# power_supply.net
KiCad netlist of a schematic drawn in Altium Designer
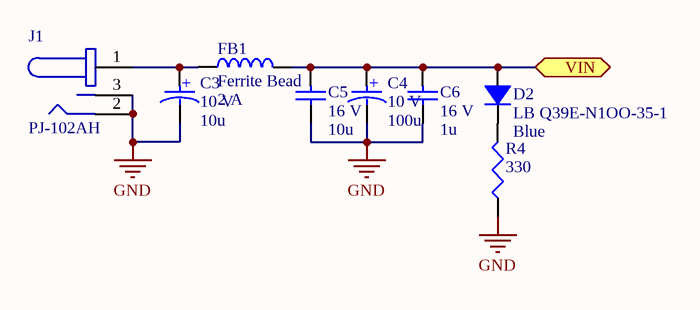
[diagram p0: power_supply.SchDoc]

(export (version "E")
  (design (tool "Eeschema 10.0.6"))
  (components
    (comp (ref "C3")
      (value "10u")
      (footprint "0603 - Polar Marking")
      (description "Tantalum capacitor, 10 uF, 10 V, 0603 package")
      (fields
        (field (name "TOLERANCE") "10%")
        (field (name "VOLTAGE RATED") "10 V")
        (field (name "Comment") "Tantalum capacitor")
      )
      (libsource (lib "rlc") (part "C_10u_10V_0603_tantalum"))
    )
    (comp (ref "C4")
      (value "100u")
      (footprint "2917")
      (description "Tantalum capacitor, 100u, 2917 package")
      (fields
        (field (name "TOLERANCE") "10%")
        (field (name "VOLTAGE RATED") "10 V")
        (field (name "Comment") "Ceramic capacitor")
      )
      (libsource (lib "rlc") (part "C_100u_10V_2917_tantalum"))
    )
    (comp (ref "C5")
      (value "10u")
      (footprint "0603")
      (description "Ceramic capacitor, 10 uF, 16 V, 0603 package")
      (fields
        (field (name "TOLERANCE") "20%")
        (field (name "VOLTAGE RATED") "16 V")
        (field (name "Comment") "Ceramic capacitor")
      )
      (libsource (lib "rlc") (part "C_10u_16V_0603_ceramic"))
    )
    (comp (ref "C6")
      (value "1u")
      (footprint "0603")
      (description "Ceramic capacitor, 1 uF, 16 V, 0603 package")
      (fields
        (field (name "TOLERANCE") "10%")
        (field (name "VOLTAGE RATED") "16 V")
        (field (name "Comment") "Ceramic capacitor")
      )
      (libsource (lib "rlc") (part "C_1u_16V_0603_ceramic"))
    )
    (comp (ref "D2")
      (value "LB Q39E-N1OO-35-1")
      (footprint "0603 - LED")
      (description "LED, Blue, 0603")
      (fields (field (name "COLOR") "Blue"))
      (libsource (lib "rlc") (part "D_LED_Blue_0603"))
    )
    (comp (ref "FB1")
      (value "Ferrite Bead")
      (footprint "0603")
      (description "Ferrite Bead, 2 A, 0603 package")
      (fields (field (name "CURRENT RATING") "2 A"))
      (libsource (lib "rlc") (part "FB_2A_0603"))
    )
    (comp (ref "J1")
      (value "PJ-102AH")
      (footprint "PJ-102AH")
      (description "CONN PWR JACK 2.1X5.5MM HIGH CUR")
      (libsource (lib "connectors") (part "PJ-102AH"))
    )
    (comp (ref "R4")
      (value "330")
      (footprint "0603")
      (description "Chip resistor, 330, 0603 package")
      (fields (field (name "TOLERANCE") "1%") (field (name "POWER") "1/10 W"))
      (libsource (lib "rlc") (part "R_330_0603"))
    )
  )
  (nets
    (net (code "1") (name "/VIN") (class "Default")
      (node (ref "C4") (pin "1") (pintype "passive"))
      (node (ref "C5") (pin "1") (pintype "passive"))
      (node (ref "C6") (pin "1") (pintype "passive"))
      (node (ref "D2") (pin "1") (pintype "passive"))
      (node (ref "FB1") (pin "1") (pintype "passive"))
    )
    (net (code "2") (name "GND") (class "Default")
      (node (ref "C3") (pin "2") (pintype "passive"))
      (node (ref "C4") (pin "2") (pintype "passive"))
      (node (ref "C5") (pin "2") (pintype "passive"))
      (node (ref "C6") (pin "2") (pintype "passive"))
      (node (ref "J1") (pin "2") (pintype "passive"))
      (node (ref "J1") (pin "3") (pintype "passive"))
      (node (ref "R4") (pin "2") (pintype "passive"))
    )
    (net (code "3") (name "Net-(C3-Pad1)") (class "Default")
      (node (ref "C3") (pin "1") (pintype "passive"))
      (node (ref "FB1") (pin "2") (pintype "passive"))
      (node (ref "J1") (pin "1") (pintype "passive"))
    )
    (net (code "4") (name "Net-(D2-Pad2)") (class "Default")
      (node (ref "D2") (pin "2") (pintype "passive"))
      (node (ref "R4") (pin "1") (pintype "passive"))
    )
  )
)
